# mic.net
KiCad netlist of a schematic drawn in EAGLE
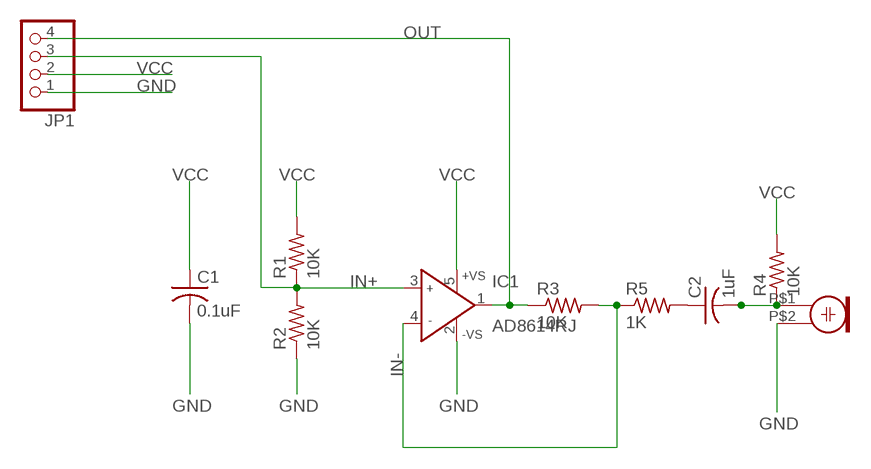
[diagram p0: schematic, sheet 1]

(export (version "E")
  (design (tool "Eeschema 10.0.6"))
  (components
    (comp (ref "C1")
      (value "0.1uF")
      (footprint "eagle-import:C1206")
      (libsource (lib "eagle-import") (part "C-USC1206"))
    )
    (comp (ref "C2")
      (value "1uF")
      (footprint "eagle-import:C1206")
      (libsource (lib "eagle-import") (part "C-USC1206"))
    )
    (comp (ref "IC1")
      (value "AD8614RJ")
      (footprint "eagle-import:SOT23-5")
      (fields (field (name "MF") "ALTERA CORPORATION") (field (name "MPN") "AD8614ARTZ-REEL7"))
      (libsource (lib "eagle-import") (part "AD8614RJ"))
    )
    (comp (ref "JP1")
      (value "PINHD-1X4")
      (footprint "eagle-import:1X04")
      (libsource (lib "eagle-import") (part "PINHD-1X4"))
    )
    (comp (ref "R1")
      (value "10K")
      (footprint "eagle-import:R1206")
      (libsource (lib "eagle-import") (part "R-US_R1206"))
    )
    (comp (ref "R2")
      (value "10K")
      (footprint "eagle-import:R1206")
      (libsource (lib "eagle-import") (part "R-US_R1206"))
    )
    (comp (ref "R3")
      (value "10K")
      (footprint "eagle-import:R1206")
      (libsource (lib "eagle-import") (part "R-US_R1206"))
    )
    (comp (ref "R4")
      (value "10K")
      (footprint "eagle-import:R1206")
      (libsource (lib "eagle-import") (part "R-US_R1206"))
    )
    (comp (ref "R5")
      (value "1K")
      (footprint "eagle-import:R1206")
      (libsource (lib "eagle-import") (part "R-US_R1206"))
    )
    (comp (ref "U$1")
      (value "ELECTRET")
      (footprint "eagle-import:ELECTRET_6MM_SMD")
      (libsource (lib "eagle-import") (part "ELECTRET"))
    )
  )
  (nets
    (net (code "1") (name "/GND") (class "Default")
      (node (ref "C1") (pin "2") (pinfunction "2_2") (pintype "passive"))
      (node (ref "IC1") (pin "2") (pinfunction "-VS_2") (pintype "input"))
      (node (ref "JP1") (pin "1") (pinfunction "1_1") (pintype "passive"))
      (node (ref "R2") (pin "1") (pinfunction "1_1") (pintype "passive"))
      (node (ref "U$1") (pin "P$2") (pinfunction "2_P$2") (pintype "passive"))
    )
    (net (code "2") (name "/IN+") (class "Default")
      (node (ref "IC1") (pin "3") (pinfunction "IN+_3") (pintype "input"))
      (node (ref "JP1") (pin "3") (pinfunction "3_3") (pintype "passive"))
      (node (ref "R1") (pin "1") (pinfunction "1_1") (pintype "passive"))
      (node (ref "R2") (pin "2") (pinfunction "2_2") (pintype "passive"))
    )
    (net (code "3") (name "/IN-") (class "Default")
      (node (ref "IC1") (pin "4") (pinfunction "IN-_4") (pintype "input"))
      (node (ref "R3") (pin "2") (pinfunction "2_2") (pintype "passive"))
      (node (ref "R5") (pin "1") (pinfunction "1_1") (pintype "passive"))
    )
    (net (code "4") (name "/OUT") (class "Default")
      (node (ref "IC1") (pin "1") (pinfunction "OUT_1") (pintype "output"))
      (node (ref "JP1") (pin "4") (pinfunction "4_4") (pintype "passive"))
      (node (ref "R3") (pin "1") (pinfunction "1_1") (pintype "passive"))
    )
    (net (code "5") (name "/VCC") (class "Default")
      (node (ref "C1") (pin "1") (pinfunction "1_1") (pintype "passive"))
      (node (ref "IC1") (pin "5") (pinfunction "+VS_5") (pintype "input"))
      (node (ref "JP1") (pin "2") (pinfunction "2_2") (pintype "passive"))
      (node (ref "R1") (pin "2") (pinfunction "2_2") (pintype "passive"))
      (node (ref "R4") (pin "2") (pinfunction "2_2") (pintype "passive"))
    )
    (net (code "6") (name "Net-(C2-Pad1)") (class "Default")
      (node (ref "C2") (pin "1") (pinfunction "1_1") (pintype "passive"))
      (node (ref "R5") (pin "2") (pinfunction "2_2") (pintype "passive"))
    )
    (net (code "7") (name "Net-(U$1-1)") (class "Default")
      (node (ref "C2") (pin "2") (pinfunction "2_2") (pintype "passive"))
      (node (ref "R4") (pin "1") (pinfunction "1_1") (pintype "passive"))
      (node (ref "U$1") (pin "P$1") (pinfunction "1_P$1") (pintype "passive"))
    )
  )
)
